# BMI160.net
KiCad netlist of a schematic drawn in Altium Designer
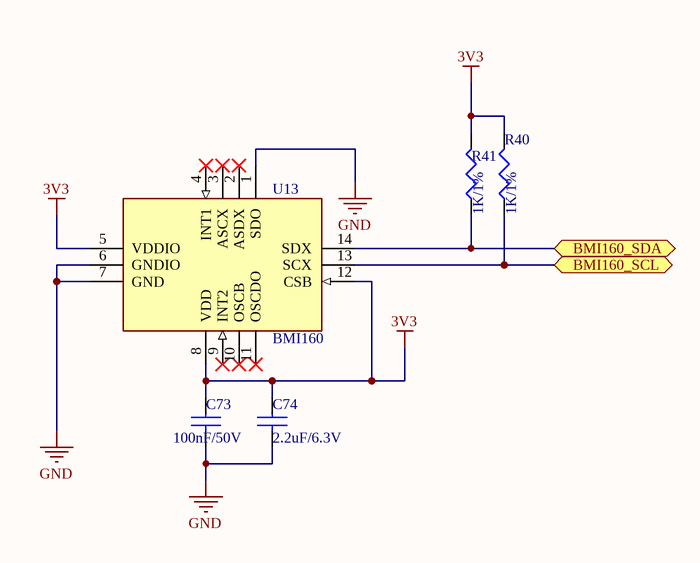
[diagram p0: BMI160.SchDoc]

(export (version "E")
  (design (tool "Eeschema 10.0.6"))
  (components
    (comp (ref "C73") (value "100nF/50V") (footprint "C0402") (libsource (lib "*") (part "CAP NP")))
    (comp (ref "C74") (value "2.2uF/6.3V") (footprint "C0402") (libsource (lib "*") (part "CAP NP")))
    (comp (ref "R40") (value "1K/1%") (footprint "R0402") (libsource (lib "*") (part "RESISTOR")))
    (comp (ref "R41") (value "1K/1%") (footprint "R0402") (libsource (lib "*") (part "RESISTOR")))
    (comp (ref "U13")
      (value "BMI160")
      (footprint "PQFN50P300X250X88-14N")
      (description "Integrated Circuit")
      (fields (field (name "MOUSER PART NUMBER") "262-BMI160"))
      (libsource (lib "VESC_DEVICE_Library") (part "BMI160"))
    )
  )
  (nets
    (net (code "1") (name "/BMI160_SCL") (class "Default")
      (node (ref "R40") (pin "1") (pinfunction "1_1") (pintype "passive"))
      (node (ref "U13") (pin "13") (pinfunction "SCX_13") (pintype "passive"))
    )
    (net (code "2") (name "/BMI160_SDA") (class "Default")
      (node (ref "R41") (pin "1") (pinfunction "1_1") (pintype "passive"))
      (node (ref "U13") (pin "14") (pinfunction "SDX_14") (pintype "passive"))
    )
    (net (code "3") (name "3V3") (class "Default")
      (node (ref "C73") (pin "1") (pinfunction "1_1") (pintype "passive"))
      (node (ref "C74") (pin "1") (pinfunction "1_1") (pintype "passive"))
      (node (ref "R40") (pin "2") (pinfunction "2_2") (pintype "passive"))
      (node (ref "R41") (pin "2") (pinfunction "2_2") (pintype "passive"))
      (node (ref "U13") (pin "12") (pinfunction "CSB_12") (pintype "input"))
      (node (ref "U13") (pin "5") (pinfunction "VDDIO_5") (pintype "power_in"))
      (node (ref "U13") (pin "8") (pinfunction "VDD_8") (pintype "power_in"))
    )
    (net (code "4") (name "GND") (class "Default")
      (node (ref "C73") (pin "2") (pinfunction "2_2") (pintype "passive"))
      (node (ref "C74") (pin "2") (pinfunction "2_2") (pintype "passive"))
      (node (ref "U13") (pin "1") (pinfunction "SDO_1") (pintype "passive"))
      (node (ref "U13") (pin "6") (pinfunction "GNDIO_6") (pintype "power_in"))
      (node (ref "U13") (pin "7") (pinfunction "GND_7") (pintype "power_in"))
    )
    (net (code "5") (name "unconnected-(U13-ASCX-Pad3)") (class "Default")
      (node (ref "U13") (pin "3") (pinfunction "ASCX_3") (pintype "passive+no_connect"))
    )
    (net (code "6") (name "unconnected-(U13-ASDX-Pad2)") (class "Default")
      (node (ref "U13") (pin "2") (pinfunction "ASDX_2") (pintype "passive+no_connect"))
    )
    (net (code "7") (name "unconnected-(U13-INT1-Pad4)") (class "Default")
      (node (ref "U13") (pin "4") (pinfunction "INT1_4") (pintype "input+no_connect"))
    )
    (net (code "8") (name "unconnected-(U13-INT2-Pad9)") (class "Default")
      (node (ref "U13") (pin "9") (pinfunction "INT2_9") (pintype "input+no_connect"))
    )
    (net (code "9") (name "unconnected-(U13-OSCB-Pad10)") (class "Default")
      (node (ref "U13") (pin "10") (pinfunction "OSCB_10") (pintype "passive+no_connect"))
    )
    (net (code "10") (name "unconnected-(U13-OSCDO-Pad11)") (class "Default")
      (node (ref "U13") (pin "11") (pinfunction "OSCDO_11") (pintype "passive+no_connect"))
    )
  )
)
